# Tx_leds.net
KiCad netlist of a schematic drawn in Altium Designer
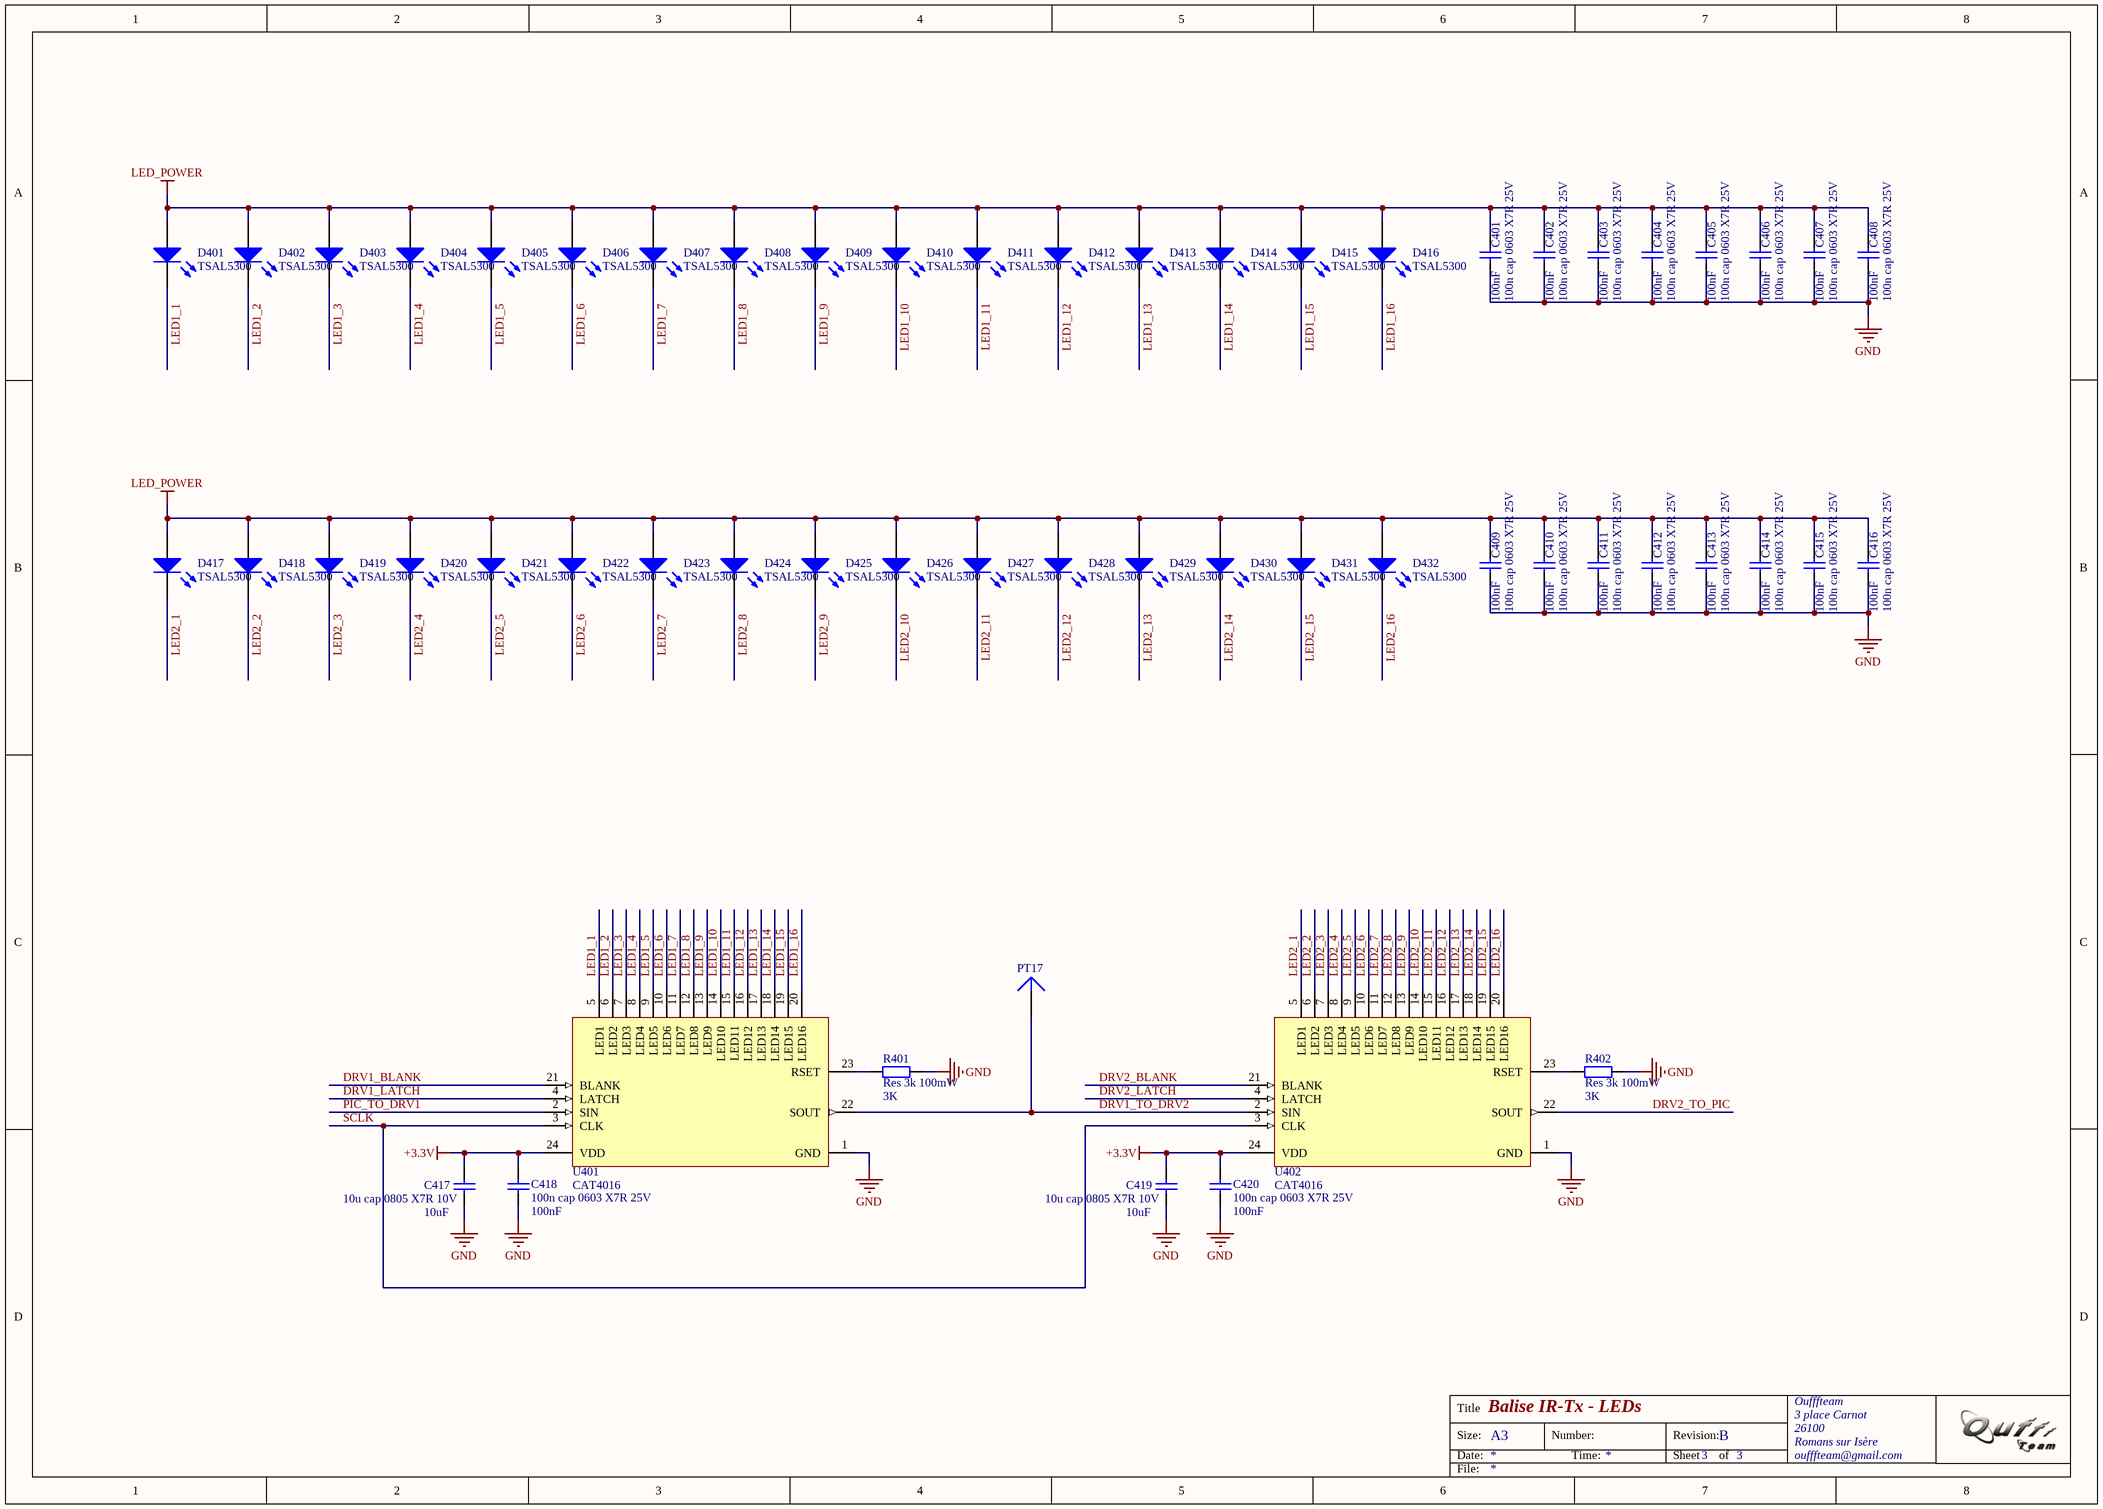
[diagram p0: Tx_leds.SchDoc]

(export (version "E")
  (design (tool "Eeschema 10.0.6"))
  (components
    (comp (ref "C401")
      (value "100n cap 0603 X7R 25V")
      (footprint "0603")
      (description "Capacitor")
      (fields (field (name "ALTIUM_VALUE") "100nF") (field (name "PUBLISHER") "Altium Limited"))
      (libsource (lib "Miscellaneous Devices") (part "Cap"))
    )
    (comp (ref "C402")
      (value "100n cap 0603 X7R 25V")
      (footprint "0603")
      (description "Capacitor")
      (fields (field (name "ALTIUM_VALUE") "100nF") (field (name "PUBLISHER") "Altium Limited"))
      (libsource (lib "Miscellaneous Devices") (part "Cap"))
    )
    (comp (ref "C403")
      (value "100n cap 0603 X7R 25V")
      (footprint "0603")
      (description "Capacitor")
      (fields (field (name "ALTIUM_VALUE") "100nF") (field (name "PUBLISHER") "Altium Limited"))
      (libsource (lib "Miscellaneous Devices") (part "Cap"))
    )
    (comp (ref "C404")
      (value "100n cap 0603 X7R 25V")
      (footprint "0603")
      (description "Capacitor")
      (fields (field (name "ALTIUM_VALUE") "100nF") (field (name "PUBLISHER") "Altium Limited"))
      (libsource (lib "Miscellaneous Devices") (part "Cap"))
    )
    (comp (ref "C405")
      (value "100n cap 0603 X7R 25V")
      (footprint "0603")
      (description "Capacitor")
      (fields (field (name "ALTIUM_VALUE") "100nF") (field (name "PUBLISHER") "Altium Limited"))
      (libsource (lib "Miscellaneous Devices") (part "Cap"))
    )
    (comp (ref "C406")
      (value "100n cap 0603 X7R 25V")
      (footprint "0603")
      (description "Capacitor")
      (fields (field (name "ALTIUM_VALUE") "100nF") (field (name "PUBLISHER") "Altium Limited"))
      (libsource (lib "Miscellaneous Devices") (part "Cap"))
    )
    (comp (ref "C407")
      (value "100n cap 0603 X7R 25V")
      (footprint "0603")
      (description "Capacitor")
      (fields (field (name "ALTIUM_VALUE") "100nF") (field (name "PUBLISHER") "Altium Limited"))
      (libsource (lib "Miscellaneous Devices") (part "Cap"))
    )
    (comp (ref "C408")
      (value "100n cap 0603 X7R 25V")
      (footprint "0603")
      (description "Capacitor")
      (fields (field (name "ALTIUM_VALUE") "100nF") (field (name "PUBLISHER") "Altium Limited"))
      (libsource (lib "Miscellaneous Devices") (part "Cap"))
    )
    (comp (ref "C409")
      (value "100n cap 0603 X7R 25V")
      (footprint "0603")
      (description "Capacitor")
      (fields (field (name "ALTIUM_VALUE") "100nF") (field (name "PUBLISHER") "Altium Limited"))
      (libsource (lib "Miscellaneous Devices") (part "Cap"))
    )
    (comp (ref "C410")
      (value "100n cap 0603 X7R 25V")
      (footprint "0603")
      (description "Capacitor")
      (fields (field (name "ALTIUM_VALUE") "100nF") (field (name "PUBLISHER") "Altium Limited"))
      (libsource (lib "Miscellaneous Devices") (part "Cap"))
    )
    (comp (ref "C411")
      (value "100n cap 0603 X7R 25V")
      (footprint "0603")
      (description "Capacitor")
      (fields (field (name "ALTIUM_VALUE") "100nF") (field (name "PUBLISHER") "Altium Limited"))
      (libsource (lib "Miscellaneous Devices") (part "Cap"))
    )
    (comp (ref "C412")
      (value "100n cap 0603 X7R 25V")
      (footprint "0603")
      (description "Capacitor")
      (fields (field (name "ALTIUM_VALUE") "100nF") (field (name "PUBLISHER") "Altium Limited"))
      (libsource (lib "Miscellaneous Devices") (part "Cap"))
    )
    (comp (ref "C413")
      (value "100n cap 0603 X7R 25V")
      (footprint "0603")
      (description "Capacitor")
      (fields (field (name "ALTIUM_VALUE") "100nF") (field (name "PUBLISHER") "Altium Limited"))
      (libsource (lib "Miscellaneous Devices") (part "Cap"))
    )
    (comp (ref "C414")
      (value "100n cap 0603 X7R 25V")
      (footprint "0603")
      (description "Capacitor")
      (fields (field (name "ALTIUM_VALUE") "100nF") (field (name "PUBLISHER") "Altium Limited"))
      (libsource (lib "Miscellaneous Devices") (part "Cap"))
    )
    (comp (ref "C415")
      (value "100n cap 0603 X7R 25V")
      (footprint "0603")
      (description "Capacitor")
      (fields (field (name "ALTIUM_VALUE") "100nF") (field (name "PUBLISHER") "Altium Limited"))
      (libsource (lib "Miscellaneous Devices") (part "Cap"))
    )
    (comp (ref "C416")
      (value "100n cap 0603 X7R 25V")
      (footprint "0603")
      (description "Capacitor")
      (fields (field (name "ALTIUM_VALUE") "100nF") (field (name "PUBLISHER") "Altium Limited"))
      (libsource (lib "Miscellaneous Devices") (part "Cap"))
    )
    (comp (ref "C417")
      (value "10u cap 0805 X7R 10V")
      (footprint "0805")
      (description "Capacitor")
      (fields (field (name "ALTIUM_VALUE") "10uF") (field (name "PUBLISHER") "Altium Limited"))
      (libsource (lib "Miscellaneous Devices") (part "Cap"))
    )
    (comp (ref "C418")
      (value "100n cap 0603 X7R 25V")
      (footprint "0603")
      (description "Capacitor")
      (fields (field (name "ALTIUM_VALUE") "100nF") (field (name "PUBLISHER") "Altium Limited"))
      (libsource (lib "Miscellaneous Devices") (part "Cap"))
    )
    (comp (ref "C419")
      (value "10u cap 0805 X7R 10V")
      (footprint "0805")
      (description "Capacitor")
      (fields (field (name "ALTIUM_VALUE") "10uF") (field (name "PUBLISHER") "Altium Limited"))
      (libsource (lib "Miscellaneous Devices") (part "Cap"))
    )
    (comp (ref "C420")
      (value "100n cap 0603 X7R 25V")
      (footprint "0603")
      (description "Capacitor")
      (fields (field (name "ALTIUM_VALUE") "100nF") (field (name "PUBLISHER") "Altium Limited"))
      (libsource (lib "Miscellaneous Devices") (part "Cap"))
    )
    (comp (ref "D401")
      (value "TSAL5300")
      (footprint "LED-1")
      (description "Typical RED GaAs LED")
      (fields (field (name "PUBLISHER") "Altium Limited"))
      (libsource (lib "Miscellaneous Devices") (part "LED1"))
    )
    (comp (ref "D402")
      (value "TSAL5300")
      (footprint "LED-1")
      (description "Typical RED GaAs LED")
      (fields (field (name "PUBLISHER") "Altium Limited"))
      (libsource (lib "Miscellaneous Devices") (part "LED1"))
    )
    (comp (ref "D403")
      (value "TSAL5300")
      (footprint "LED-1")
      (description "Typical RED GaAs LED")
      (fields (field (name "PUBLISHER") "Altium Limited"))
      (libsource (lib "Miscellaneous Devices") (part "LED1"))
    )
    (comp (ref "D404")
      (value "TSAL5300")
      (footprint "LED-1")
      (description "Typical RED GaAs LED")
      (fields (field (name "PUBLISHER") "Altium Limited"))
      (libsource (lib "Miscellaneous Devices") (part "LED1"))
    )
    (comp (ref "D405")
      (value "TSAL5300")
      (footprint "LED-1")
      (description "Typical RED GaAs LED")
      (fields (field (name "PUBLISHER") "Altium Limited"))
      (libsource (lib "Miscellaneous Devices") (part "LED1"))
    )
    (comp (ref "D406")
      (value "TSAL5300")
      (footprint "LED-1")
      (description "Typical RED GaAs LED")
      (fields (field (name "PUBLISHER") "Altium Limited"))
      (libsource (lib "Miscellaneous Devices") (part "LED1"))
    )
    (comp (ref "D407")
      (value "TSAL5300")
      (footprint "LED-1")
      (description "Typical RED GaAs LED")
      (fields (field (name "PUBLISHER") "Altium Limited"))
      (libsource (lib "Miscellaneous Devices") (part "LED1"))
    )
    (comp (ref "D408")
      (value "TSAL5300")
      (footprint "LED-1")
      (description "Typical RED GaAs LED")
      (fields (field (name "PUBLISHER") "Altium Limited"))
      (libsource (lib "Miscellaneous Devices") (part "LED1"))
    )
    (comp (ref "D409")
      (value "TSAL5300")
      (footprint "LED-1")
      (description "Typical RED GaAs LED")
      (fields (field (name "PUBLISHER") "Altium Limited"))
      (libsource (lib "Miscellaneous Devices") (part "LED1"))
    )
    (comp (ref "D410")
      (value "TSAL5300")
      (footprint "LED-1")
      (description "Typical RED GaAs LED")
      (fields (field (name "PUBLISHER") "Altium Limited"))
      (libsource (lib "Miscellaneous Devices") (part "LED1"))
    )
    (comp (ref "D411")
      (value "TSAL5300")
      (footprint "LED-1")
      (description "Typical RED GaAs LED")
      (fields (field (name "PUBLISHER") "Altium Limited"))
      (libsource (lib "Miscellaneous Devices") (part "LED1"))
    )
    (comp (ref "D412")
      (value "TSAL5300")
      (footprint "LED-1")
      (description "Typical RED GaAs LED")
      (fields (field (name "PUBLISHER") "Altium Limited"))
      (libsource (lib "Miscellaneous Devices") (part "LED1"))
    )
    (comp (ref "D413")
      (value "TSAL5300")
      (footprint "LED-1")
      (description "Typical RED GaAs LED")
      (fields (field (name "PUBLISHER") "Altium Limited"))
      (libsource (lib "Miscellaneous Devices") (part "LED1"))
    )
    (comp (ref "D414")
      (value "TSAL5300")
      (footprint "LED-1")
      (description "Typical RED GaAs LED")
      (fields (field (name "PUBLISHER") "Altium Limited"))
      (libsource (lib "Miscellaneous Devices") (part "LED1"))
    )
    (comp (ref "D415")
      (value "TSAL5300")
      (footprint "LED-1")
      (description "Typical RED GaAs LED")
      (fields (field (name "PUBLISHER") "Altium Limited"))
      (libsource (lib "Miscellaneous Devices") (part "LED1"))
    )
    (comp (ref "D416")
      (value "TSAL5300")
      (footprint "LED-1")
      (description "Typical RED GaAs LED")
      (fields (field (name "PUBLISHER") "Altium Limited"))
      (libsource (lib "Miscellaneous Devices") (part "LED1"))
    )
    (comp (ref "D417")
      (value "TSAL5300")
      (footprint "LED-1")
      (description "Typical RED GaAs LED")
      (fields (field (name "PUBLISHER") "Altium Limited"))
      (libsource (lib "Miscellaneous Devices") (part "LED1"))
    )
    (comp (ref "D418")
      (value "TSAL5300")
      (footprint "LED-1")
      (description "Typical RED GaAs LED")
      (fields (field (name "PUBLISHER") "Altium Limited"))
      (libsource (lib "Miscellaneous Devices") (part "LED1"))
    )
    (comp (ref "D419")
      (value "TSAL5300")
      (footprint "LED-1")
      (description "Typical RED GaAs LED")
      (fields (field (name "PUBLISHER") "Altium Limited"))
      (libsource (lib "Miscellaneous Devices") (part "LED1"))
    )
    (comp (ref "D420")
      (value "TSAL5300")
      (footprint "LED-1")
      (description "Typical RED GaAs LED")
      (fields (field (name "PUBLISHER") "Altium Limited"))
      (libsource (lib "Miscellaneous Devices") (part "LED1"))
    )
    (comp (ref "D421")
      (value "TSAL5300")
      (footprint "LED-1")
      (description "Typical RED GaAs LED")
      (fields (field (name "PUBLISHER") "Altium Limited"))
      (libsource (lib "Miscellaneous Devices") (part "LED1"))
    )
    (comp (ref "D422")
      (value "TSAL5300")
      (footprint "LED-1")
      (description "Typical RED GaAs LED")
      (fields (field (name "PUBLISHER") "Altium Limited"))
      (libsource (lib "Miscellaneous Devices") (part "LED1"))
    )
    (comp (ref "D423")
      (value "TSAL5300")
      (footprint "LED-1")
      (description "Typical RED GaAs LED")
      (fields (field (name "PUBLISHER") "Altium Limited"))
      (libsource (lib "Miscellaneous Devices") (part "LED1"))
    )
    (comp (ref "D424")
      (value "TSAL5300")
      (footprint "LED-1")
      (description "Typical RED GaAs LED")
      (fields (field (name "PUBLISHER") "Altium Limited"))
      (libsource (lib "Miscellaneous Devices") (part "LED1"))
    )
    (comp (ref "D425")
      (value "TSAL5300")
      (footprint "LED-1")
      (description "Typical RED GaAs LED")
      (fields (field (name "PUBLISHER") "Altium Limited"))
      (libsource (lib "Miscellaneous Devices") (part "LED1"))
    )
    (comp (ref "D426")
      (value "TSAL5300")
      (footprint "LED-1")
      (description "Typical RED GaAs LED")
      (fields (field (name "PUBLISHER") "Altium Limited"))
      (libsource (lib "Miscellaneous Devices") (part "LED1"))
    )
    (comp (ref "D427")
      (value "TSAL5300")
      (footprint "LED-1")
      (description "Typical RED GaAs LED")
      (fields (field (name "PUBLISHER") "Altium Limited"))
      (libsource (lib "Miscellaneous Devices") (part "LED1"))
    )
    (comp (ref "D428")
      (value "TSAL5300")
      (footprint "LED-1")
      (description "Typical RED GaAs LED")
      (fields (field (name "PUBLISHER") "Altium Limited"))
      (libsource (lib "Miscellaneous Devices") (part "LED1"))
    )
    (comp (ref "D429")
      (value "TSAL5300")
      (footprint "LED-1")
      (description "Typical RED GaAs LED")
      (fields (field (name "PUBLISHER") "Altium Limited"))
      (libsource (lib "Miscellaneous Devices") (part "LED1"))
    )
    (comp (ref "D430")
      (value "TSAL5300")
      (footprint "LED-1")
      (description "Typical RED GaAs LED")
      (fields (field (name "PUBLISHER") "Altium Limited"))
      (libsource (lib "Miscellaneous Devices") (part "LED1"))
    )
    (comp (ref "D431")
      (value "TSAL5300")
      (footprint "LED-1")
      (description "Typical RED GaAs LED")
      (fields (field (name "PUBLISHER") "Altium Limited"))
      (libsource (lib "Miscellaneous Devices") (part "LED1"))
    )
    (comp (ref "D432")
      (value "TSAL5300")
      (footprint "LED-1")
      (description "Typical RED GaAs LED")
      (fields (field (name "PUBLISHER") "Altium Limited"))
      (libsource (lib "Miscellaneous Devices") (part "LED1"))
    )
    (comp (ref "PT17")
      (value "Plug")
      (footprint "TP")
      (fields (field (name "PUBLISHER") "Altium Limited"))
      (libsource (lib "Miscellaneous Connectors") (part "Plug"))
    )
    (comp (ref "R401")
      (value "Res 3k 100mW")
      (footprint "0603")
      (description "Resistor")
      (fields (field (name "ALTIUM_VALUE") "3K") (field (name "PUBLISHER") "Altium Limited"))
      (libsource (lib "Miscellaneous Devices") (part "Res2"))
    )
    (comp (ref "R402")
      (value "Res 3k 100mW")
      (footprint "0603")
      (description "Resistor")
      (fields (field (name "ALTIUM_VALUE") "3K") (field (name "PUBLISHER") "Altium Limited"))
      (libsource (lib "Miscellaneous Devices") (part "Res2"))
    )
    (comp (ref "U401")
      (value "CAT4016")
      (footprint "TSSOP65P640X120-24L")
      (description "16-Channel Constant Current LED Driver")
      (libsource (lib "Oufff_Lib2") (part "CAT4016"))
    )
    (comp (ref "U402")
      (value "CAT4016")
      (footprint "TSSOP65P640X120-24L")
      (description "16-Channel Constant Current LED Driver")
      (libsource (lib "Oufff_Lib2") (part "CAT4016"))
    )
  )
  (nets
    (net (code "1") (name "+3.3V") (class "Default")
      (node (ref "C417") (pin "2") (pinfunction "2_2") (pintype "passive"))
      (node (ref "C418") (pin "2") (pinfunction "2_2") (pintype "passive"))
      (node (ref "C419") (pin "2") (pinfunction "2_2") (pintype "passive"))
      (node (ref "C420") (pin "2") (pinfunction "2_2") (pintype "passive"))
      (node (ref "U401") (pin "24") (pinfunction "VDD_24") (pintype "power_in"))
      (node (ref "U402") (pin "24") (pinfunction "VDD_24") (pintype "power_in"))
    )
    (net (code "2") (name "/DRV1_BLANK") (class "Default")
      (node (ref "U401") (pin "21") (pinfunction "BLANK_21") (pintype "input"))
    )
    (net (code "3") (name "/DRV1_LATCH") (class "Default")
      (node (ref "U401") (pin "4") (pinfunction "LATCH_4") (pintype "input"))
    )
    (net (code "4") (name "/DRV1_TO_DRV2") (class "Default")
      (node (ref "PT17") (pin "1") (pinfunction "1_1") (pintype "passive"))
      (node (ref "U401") (pin "22") (pinfunction "SOUT_22") (pintype "output"))
      (node (ref "U402") (pin "2") (pinfunction "SIN_2") (pintype "input"))
    )
    (net (code "5") (name "/DRV2_BLANK") (class "Default")
      (node (ref "U402") (pin "21") (pinfunction "BLANK_21") (pintype "input"))
    )
    (net (code "6") (name "/DRV2_LATCH") (class "Default")
      (node (ref "U402") (pin "4") (pinfunction "LATCH_4") (pintype "input"))
    )
    (net (code "7") (name "/DRV2_TO_PIC") (class "Default")
      (node (ref "U402") (pin "22") (pinfunction "SOUT_22") (pintype "output"))
    )
    (net (code "8") (name "/LED1_1") (class "Default")
      (node (ref "D401") (pin "2") (pinfunction "K_2") (pintype "passive"))
      (node (ref "U401") (pin "5") (pinfunction "LED1_5") (pintype "power_in"))
    )
    (net (code "9") (name "/LED1_2") (class "Default")
      (node (ref "D402") (pin "2") (pinfunction "K_2") (pintype "passive"))
      (node (ref "U401") (pin "6") (pinfunction "LED2_6") (pintype "power_in"))
    )
    (net (code "10") (name "/LED1_3") (class "Default")
      (node (ref "D403") (pin "2") (pinfunction "K_2") (pintype "passive"))
      (node (ref "U401") (pin "7") (pinfunction "LED3_7") (pintype "power_in"))
    )
    (net (code "11") (name "/LED1_4") (class "Default")
      (node (ref "D404") (pin "2") (pinfunction "K_2") (pintype "passive"))
      (node (ref "U401") (pin "8") (pinfunction "LED4_8") (pintype "power_in"))
    )
    (net (code "12") (name "/LED1_5") (class "Default")
      (node (ref "D405") (pin "2") (pinfunction "K_2") (pintype "passive"))
      (node (ref "U401") (pin "9") (pinfunction "LED5_9") (pintype "power_in"))
    )
    (net (code "13") (name "/LED1_6") (class "Default")
      (node (ref "D406") (pin "2") (pinfunction "K_2") (pintype "passive"))
      (node (ref "U401") (pin "10") (pinfunction "LED6_10") (pintype "power_in"))
    )
    (net (code "14") (name "/LED1_7") (class "Default")
      (node (ref "D407") (pin "2") (pinfunction "K_2") (pintype "passive"))
      (node (ref "U401") (pin "11") (pinfunction "LED7_11") (pintype "power_in"))
    )
    (net (code "15") (name "/LED1_8") (class "Default")
      (node (ref "D408") (pin "2") (pinfunction "K_2") (pintype "passive"))
      (node (ref "U401") (pin "12") (pinfunction "LED8_12") (pintype "power_in"))
    )
    (net (code "16") (name "/LED1_9") (class "Default")
      (node (ref "D409") (pin "2") (pinfunction "K_2") (pintype "passive"))
      (node (ref "U401") (pin "13") (pinfunction "LED9_13") (pintype "power_in"))
    )
    (net (code "17") (name "/LED1_10") (class "Default")
      (node (ref "D410") (pin "2") (pinfunction "K_2") (pintype "passive"))
      (node (ref "U401") (pin "14") (pinfunction "LED10_14") (pintype "power_in"))
    )
    (net (code "18") (name "/LED1_11") (class "Default")
      (node (ref "D411") (pin "2") (pinfunction "K_2") (pintype "passive"))
      (node (ref "U401") (pin "15") (pinfunction "LED11_15") (pintype "power_in"))
    )
    (net (code "19") (name "/LED1_12") (class "Default")
      (node (ref "D412") (pin "2") (pinfunction "K_2") (pintype "passive"))
      (node (ref "U401") (pin "16") (pinfunction "LED12_16") (pintype "power_in"))
    )
    (net (code "20") (name "/LED1_13") (class "Default")
      (node (ref "D413") (pin "2") (pinfunction "K_2") (pintype "passive"))
      (node (ref "U401") (pin "17") (pinfunction "LED13_17") (pintype "power_in"))
    )
    (net (code "21") (name "/LED1_14") (class "Default")
      (node (ref "D414") (pin "2") (pinfunction "K_2") (pintype "passive"))
      (node (ref "U401") (pin "18") (pinfunction "LED14_18") (pintype "power_in"))
    )
    (net (code "22") (name "/LED1_15") (class "Default")
      (node (ref "D415") (pin "2") (pinfunction "K_2") (pintype "passive"))
      (node (ref "U401") (pin "19") (pinfunction "LED15_19") (pintype "power_in"))
    )
    (net (code "23") (name "/LED1_16") (class "Default")
      (node (ref "D416") (pin "2") (pinfunction "K_2") (pintype "passive"))
      (node (ref "U401") (pin "20") (pinfunction "LED16_20") (pintype "power_in"))
    )
    (net (code "24") (name "/LED2_1") (class "Default")
      (node (ref "D417") (pin "2") (pinfunction "K_2") (pintype "passive"))
      (node (ref "U402") (pin "5") (pinfunction "LED1_5") (pintype "power_in"))
    )
    (net (code "25") (name "/LED2_2") (class "Default")
      (node (ref "D418") (pin "2") (pinfunction "K_2") (pintype "passive"))
      (node (ref "U402") (pin "6") (pinfunction "LED2_6") (pintype "power_in"))
    )
    (net (code "26") (name "/LED2_3") (class "Default")
      (node (ref "D419") (pin "2") (pinfunction "K_2") (pintype "passive"))
      (node (ref "U402") (pin "7") (pinfunction "LED3_7") (pintype "power_in"))
    )
    (net (code "27") (name "/LED2_4") (class "Default")
      (node (ref "D420") (pin "2") (pinfunction "K_2") (pintype "passive"))
      (node (ref "U402") (pin "8") (pinfunction "LED4_8") (pintype "power_in"))
    )
    (net (code "28") (name "/LED2_5") (class "Default")
      (node (ref "D421") (pin "2") (pinfunction "K_2") (pintype "passive"))
      (node (ref "U402") (pin "9") (pinfunction "LED5_9") (pintype "power_in"))
    )
    (net (code "29") (name "/LED2_6") (class "Default")
      (node (ref "D422") (pin "2") (pinfunction "K_2") (pintype "passive"))
      (node (ref "U402") (pin "10") (pinfunction "LED6_10") (pintype "power_in"))
    )
    (net (code "30") (name "/LED2_7") (class "Default")
      (node (ref "D423") (pin "2") (pinfunction "K_2") (pintype "passive"))
      (node (ref "U402") (pin "11") (pinfunction "LED7_11") (pintype "power_in"))
    )
    (net (code "31") (name "/LED2_8") (class "Default")
      (node (ref "D424") (pin "2") (pinfunction "K_2") (pintype "passive"))
      (node (ref "U402") (pin "12") (pinfunction "LED8_12") (pintype "power_in"))
    )
    (net (code "32") (name "/LED2_9") (class "Default")
      (node (ref "D425") (pin "2") (pinfunction "K_2") (pintype "passive"))
      (node (ref "U402") (pin "13") (pinfunction "LED9_13") (pintype "power_in"))
    )
    (net (code "33") (name "/LED2_10") (class "Default")
      (node (ref "D426") (pin "2") (pinfunction "K_2") (pintype "passive"))
      (node (ref "U402") (pin "14") (pinfunction "LED10_14") (pintype "power_in"))
    )
    (net (code "34") (name "/LED2_11") (class "Default")
      (node (ref "D427") (pin "2") (pinfunction "K_2") (pintype "passive"))
      (node (ref "U402") (pin "15") (pinfunction "LED11_15") (pintype "power_in"))
    )
    (net (code "35") (name "/LED2_12") (class "Default")
      (node (ref "D428") (pin "2") (pinfunction "K_2") (pintype "passive"))
      (node (ref "U402") (pin "16") (pinfunction "LED12_16") (pintype "power_in"))
    )
    (net (code "36") (name "/LED2_13") (class "Default")
      (node (ref "D429") (pin "2") (pinfunction "K_2") (pintype "passive"))
      (node (ref "U402") (pin "17") (pinfunction "LED13_17") (pintype "power_in"))
    )
    (net (code "37") (name "/LED2_14") (class "Default")
      (node (ref "D430") (pin "2") (pinfunction "K_2") (pintype "passive"))
      (node (ref "U402") (pin "18") (pinfunction "LED14_18") (pintype "power_in"))
    )
    (net (code "38") (name "/LED2_15") (class "Default")
      (node (ref "D431") (pin "2") (pinfunction "K_2") (pintype "passive"))
      (node (ref "U402") (pin "19") (pinfunction "LED15_19") (pintype "power_in"))
    )
    (net (code "39") (name "/LED2_16") (class "Default")
      (node (ref "D432") (pin "2") (pinfunction "K_2") (pintype "passive"))
      (node (ref "U402") (pin "20") (pinfunction "LED16_20") (pintype "power_in"))
    )
    (net (code "40") (name "/PIC_TO_DRV1") (class "Default")
      (node (ref "U401") (pin "2") (pinfunction "SIN_2") (pintype "input"))
    )
    (net (code "41") (name "/SCLK") (class "Default")
      (node (ref "U401") (pin "3") (pinfunction "CLK_3") (pintype "input"))
      (node (ref "U402") (pin "3") (pinfunction "CLK_3") (pintype "input"))
    )
    (net (code "42") (name "GND") (class "Default")
      (node (ref "C401") (pin "1") (pinfunction "1_1") (pintype "passive"))
      (node (ref "C402") (pin "1") (pinfunction "1_1") (pintype "passive"))
      (node (ref "C403") (pin "1") (pinfunction "1_1") (pintype "passive"))
      (node (ref "C404") (pin "1") (pinfunction "1_1") (pintype "passive"))
      (node (ref "C405") (pin "1") (pinfunction "1_1") (pintype "passive"))
      (node (ref "C406") (pin "1") (pinfunction "1_1") (pintype "passive"))
      (node (ref "C407") (pin "1") (pinfunction "1_1") (pintype "passive"))
      (node (ref "C408") (pin "1") (pinfunction "1_1") (pintype "passive"))
      (node (ref "C409") (pin "1") (pinfunction "1_1") (pintype "passive"))
      (node (ref "C410") (pin "1") (pinfunction "1_1") (pintype "passive"))
      (node (ref "C411") (pin "1") (pinfunction "1_1") (pintype "passive"))
      (node (ref "C412") (pin "1") (pinfunction "1_1") (pintype "passive"))
      (node (ref "C413") (pin "1") (pinfunction "1_1") (pintype "passive"))
      (node (ref "C414") (pin "1") (pinfunction "1_1") (pintype "passive"))
      (node (ref "C415") (pin "1") (pinfunction "1_1") (pintype "passive"))
      (node (ref "C416") (pin "1") (pinfunction "1_1") (pintype "passive"))
      (node (ref "C417") (pin "1") (pinfunction "1_1") (pintype "passive"))
      (node (ref "C418") (pin "1") (pinfunction "1_1") (pintype "passive"))
      (node (ref "C419") (pin "1") (pinfunction "1_1") (pintype "passive"))
      (node (ref "C420") (pin "1") (pinfunction "1_1") (pintype "passive"))
      (node (ref "R401") (pin "2") (pinfunction "2_2") (pintype "passive"))
      (node (ref "R402") (pin "2") (pinfunction "2_2") (pintype "passive"))
      (node (ref "U401") (pin "1") (pinfunction "GND_1") (pintype "power_in"))
      (node (ref "U402") (pin "1") (pinfunction "GND_1") (pintype "power_in"))
    )
    (net (code "43") (name "LED_POWER") (class "Default")
      (node (ref "C401") (pin "2") (pinfunction "2_2") (pintype "passive"))
      (node (ref "C402") (pin "2") (pinfunction "2_2") (pintype "passive"))
      (node (ref "C403") (pin "2") (pinfunction "2_2") (pintype "passive"))
      (node (ref "C404") (pin "2") (pinfunction "2_2") (pintype "passive"))
      (node (ref "C405") (pin "2") (pinfunction "2_2") (pintype "passive"))
      (node (ref "C406") (pin "2") (pinfunction "2_2") (pintype "passive"))
      (node (ref "C407") (pin "2") (pinfunction "2_2") (pintype "passive"))
      (node (ref "C408") (pin "2") (pinfunction "2_2") (pintype "passive"))
      (node (ref "C409") (pin "2") (pinfunction "2_2") (pintype "passive"))
      (node (ref "C410") (pin "2") (pinfunction "2_2") (pintype "passive"))
      (node (ref "C411") (pin "2") (pinfunction "2_2") (pintype "passive"))
      (node (ref "C412") (pin "2") (pinfunction "2_2") (pintype "passive"))
      (node (ref "C413") (pin "2") (pinfunction "2_2") (pintype "passive"))
      (node (ref "C414") (pin "2") (pinfunction "2_2") (pintype "passive"))
      (node (ref "C415") (pin "2") (pinfunction "2_2") (pintype "passive"))
      (node (ref "C416") (pin "2") (pinfunction "2_2") (pintype "passive"))
      (node (ref "D401") (pin "1") (pinfunction "A_1") (pintype "passive"))
      (node (ref "D402") (pin "1") (pinfunction "A_1") (pintype "passive"))
      (node (ref "D403") (pin "1") (pinfunction "A_1") (pintype "passive"))
      (node (ref "D404") (pin "1") (pinfunction "A_1") (pintype "passive"))
      (node (ref "D405") (pin "1") (pinfunction "A_1") (pintype "passive"))
      (node (ref "D406") (pin "1") (pinfunction "A_1") (pintype "passive"))
      (node (ref "D407") (pin "1") (pinfunction "A_1") (pintype "passive"))
      (node (ref "D408") (pin "1") (pinfunction "A_1") (pintype "passive"))
      (node (ref "D409") (pin "1") (pinfunction "A_1") (pintype "passive"))
      (node (ref "D410") (pin "1") (pinfunction "A_1") (pintype "passive"))
      (node (ref "D411") (pin "1") (pinfunction "A_1") (pintype "passive"))
      (node (ref "D412") (pin "1") (pinfunction "A_1") (pintype "passive"))
      (node (ref "D413") (pin "1") (pinfunction "A_1") (pintype "passive"))
      (node (ref "D414") (pin "1") (pinfunction "A_1") (pintype "passive"))
      (node (ref "D415") (pin "1") (pinfunction "A_1") (pintype "passive"))
      (node (ref "D416") (pin "1") (pinfunction "A_1") (pintype "passive"))
      (node (ref "D417") (pin "1") (pinfunction "A_1") (pintype "passive"))
      (node (ref "D418") (pin "1") (pinfunction "A_1") (pintype "passive"))
      (node (ref "D419") (pin "1") (pinfunction "A_1") (pintype "passive"))
      (node (ref "D420") (pin "1") (pinfunction "A_1") (pintype "passive"))
      (node (ref "D421") (pin "1") (pinfunction "A_1") (pintype "passive"))
      (node (ref "D422") (pin "1") (pinfunction "A_1") (pintype "passive"))
      (node (ref "D423") (pin "1") (pinfunction "A_1") (pintype "passive"))
      (node (ref "D424") (pin "1") (pinfunction "A_1") (pintype "passive"))
      (node (ref "D425") (pin "1") (pinfunction "A_1") (pintype "passive"))
      (node (ref "D426") (pin "1") (pinfunction "A_1") (pintype "passive"))
      (node (ref "D427") (pin "1") (pinfunction "A_1") (pintype "passive"))
      (node (ref "D428") (pin "1") (pinfunction "A_1") (pintype "passive"))
      (node (ref "D429") (pin "1") (pinfunction "A_1") (pintype "passive"))
      (node (ref "D430") (pin "1") (pinfunction "A_1") (pintype "passive"))
      (node (ref "D431") (pin "1") (pinfunction "A_1") (pintype "passive"))
      (node (ref "D432") (pin "1") (pinfunction "A_1") (pintype "passive"))
    )
    (net (code "44") (name "Net-(U401-RSET)") (class "Default")
      (node (ref "R401") (pin "1") (pinfunction "1_1") (pintype "passive"))
      (node (ref "U401") (pin "23") (pinfunction "RSET_23") (pintype "passive"))
    )
    (net (code "45") (name "Net-(U402-RSET)") (class "Default")
      (node (ref "R402") (pin "1") (pinfunction "1_1") (pintype "passive"))
      (node (ref "U402") (pin "23") (pinfunction "RSET_23") (pintype "passive"))
    )
  )
)
